# pro_mini_2_clamps.net
KiCad netlist of a schematic drawn in EAGLE
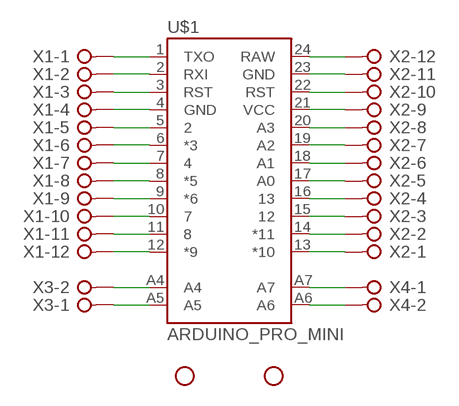
[diagram p0: schematic, sheet 1]

(export (version "E")
  (design (tool "Eeschema 10.0.6"))
  (components
    (comp (ref "STANDOFF1")
      (value "STAND-OFF")
      (footprint "eagle-import:STAND-OFF")
      (libsource (lib "eagle-import") (part "STAND-OFF"))
    )
    (comp (ref "STANDOFF2")
      (value "STAND-OFF")
      (footprint "eagle-import:STAND-OFF")
      (libsource (lib "eagle-import") (part "STAND-OFF"))
    )
    (comp (ref "U$1")
      (value "ARDUINO_PRO_MINI")
      (footprint "eagle-import:ARDUINO_PRO_MINI")
      (libsource (lib "eagle-import") (part "ARDUINO_PRO_MINI"))
    )
    (comp (ref "X1")
      (value "W237-12P")
      (footprint "eagle-import:W237-12P")
      (libsource (lib "eagle-import") (part "W237-12P"))
    )
    (comp (ref "X2")
      (value "W237-12P")
      (footprint "eagle-import:W237-12P")
      (libsource (lib "eagle-import") (part "W237-12P"))
    )
    (comp (ref "X3")
      (value "W237-02P")
      (footprint "eagle-import:W237-132")
      (libsource (lib "eagle-import") (part "W237-02P"))
    )
    (comp (ref "X4")
      (value "W237-02P")
      (footprint "eagle-import:W237-132")
      (libsource (lib "eagle-import") (part "W237-02P"))
    )
  )
  (nets
    (net (code "1") (name "Net-(U$1-*3)") (class "Default")
      (node (ref "U$1") (pin "6") (pinfunction "*3_6") (pintype "bidirectional"))
      (node (ref "X1") (pin "6") (pinfunction "KL_6") (pintype "passive"))
    )
    (net (code "2") (name "Net-(U$1-*5)") (class "Default")
      (node (ref "U$1") (pin "8") (pinfunction "*5_8") (pintype "bidirectional"))
      (node (ref "X1") (pin "8") (pinfunction "KL_8") (pintype "passive"))
    )
    (net (code "3") (name "Net-(U$1-*6)") (class "Default")
      (node (ref "U$1") (pin "9") (pinfunction "*6_9") (pintype "bidirectional"))
      (node (ref "X1") (pin "9") (pinfunction "KL_9") (pintype "passive"))
    )
    (net (code "4") (name "Net-(U$1-*9)") (class "Default")
      (node (ref "U$1") (pin "12") (pinfunction "*9_12") (pintype "bidirectional"))
      (node (ref "X1") (pin "12") (pinfunction "KL_12") (pintype "passive"))
    )
    (net (code "5") (name "Net-(U$1-*10)") (class "Default")
      (node (ref "U$1") (pin "13") (pinfunction "*10_13") (pintype "bidirectional"))
      (node (ref "X2") (pin "1") (pinfunction "KL_1") (pintype "passive"))
    )
    (net (code "6") (name "Net-(U$1-*11)") (class "Default")
      (node (ref "U$1") (pin "14") (pinfunction "*11_14") (pintype "bidirectional"))
      (node (ref "X2") (pin "2") (pinfunction "KL_2") (pintype "passive"))
    )
    (net (code "7") (name "Net-(U$1-2)") (class "Default")
      (node (ref "U$1") (pin "5") (pinfunction "2_5") (pintype "bidirectional"))
      (node (ref "X1") (pin "5") (pinfunction "KL_5") (pintype "passive"))
    )
    (net (code "8") (name "Net-(U$1-4)") (class "Default")
      (node (ref "U$1") (pin "7") (pinfunction "4_7") (pintype "bidirectional"))
      (node (ref "X1") (pin "7") (pinfunction "KL_7") (pintype "passive"))
    )
    (net (code "9") (name "Net-(U$1-7)") (class "Default")
      (node (ref "U$1") (pin "10") (pinfunction "7_10") (pintype "bidirectional"))
      (node (ref "X1") (pin "10") (pinfunction "KL_10") (pintype "passive"))
    )
    (net (code "10") (name "Net-(U$1-8)") (class "Default")
      (node (ref "U$1") (pin "11") (pinfunction "8_11") (pintype "bidirectional"))
      (node (ref "X1") (pin "11") (pinfunction "KL_11") (pintype "passive"))
    )
    (net (code "11") (name "Net-(U$1-12)") (class "Default")
      (node (ref "U$1") (pin "15") (pinfunction "12_15") (pintype "bidirectional"))
      (node (ref "X2") (pin "3") (pinfunction "KL_3") (pintype "passive"))
    )
    (net (code "12") (name "Net-(U$1-13)") (class "Default")
      (node (ref "U$1") (pin "16") (pinfunction "13_16") (pintype "bidirectional"))
      (node (ref "X2") (pin "4") (pinfunction "KL_4") (pintype "passive"))
    )
    (net (code "13") (name "Net-(U$1-A0)") (class "Default")
      (node (ref "U$1") (pin "17") (pinfunction "A0_17") (pintype "bidirectional"))
      (node (ref "X2") (pin "5") (pinfunction "KL_5") (pintype "passive"))
    )
    (net (code "14") (name "Net-(U$1-A1)") (class "Default")
      (node (ref "U$1") (pin "18") (pinfunction "A1_18") (pintype "bidirectional"))
      (node (ref "X2") (pin "6") (pinfunction "KL_6") (pintype "passive"))
    )
    (net (code "15") (name "Net-(U$1-A2)") (class "Default")
      (node (ref "U$1") (pin "19") (pinfunction "A2_19") (pintype "bidirectional"))
      (node (ref "X2") (pin "7") (pinfunction "KL_7") (pintype "passive"))
    )
    (net (code "16") (name "Net-(U$1-A3)") (class "Default")
      (node (ref "U$1") (pin "20") (pinfunction "A3_20") (pintype "bidirectional"))
      (node (ref "X2") (pin "8") (pinfunction "KL_8") (pintype "passive"))
    )
    (net (code "17") (name "Net-(U$1-RAW)") (class "Default")
      (node (ref "U$1") (pin "24") (pinfunction "RAW_24") (pintype "bidirectional"))
      (node (ref "X2") (pin "12") (pinfunction "KL_12") (pintype "passive"))
    )
    (net (code "18") (name "Net-(U$1-RXI)") (class "Default")
      (node (ref "U$1") (pin "2") (pinfunction "RXI_2") (pintype "bidirectional"))
      (node (ref "X1") (pin "2") (pinfunction "KL_2") (pintype "passive"))
    )
    (net (code "19") (name "Net-(U$1-TXO)") (class "Default")
      (node (ref "U$1") (pin "1") (pinfunction "TXO_1") (pintype "bidirectional"))
      (node (ref "X1") (pin "1") (pinfunction "KL_1") (pintype "passive"))
    )
    (net (code "20") (name "Net-(U$1-VCC)") (class "Default")
      (node (ref "U$1") (pin "21") (pinfunction "VCC_21") (pintype "bidirectional"))
      (node (ref "X2") (pin "9") (pinfunction "KL_9") (pintype "passive"))
    )
    (net (code "21") (name "Net-(X1F-KL)") (class "Default")
      (node (ref "U$1") (pin "3") (pinfunction "RST_3") (pintype "bidirectional"))
      (node (ref "X1") (pin "3") (pinfunction "KL_3") (pintype "passive"))
    )
    (net (code "22") (name "Net-(X1G-KL)") (class "Default")
      (node (ref "U$1") (pin "4") (pinfunction "GND_4") (pintype "bidirectional"))
      (node (ref "X1") (pin "4") (pinfunction "KL_4") (pintype "passive"))
    )
    (net (code "23") (name "Net-(X2B-KL)") (class "Default")
      (node (ref "U$1") (pin "22") (pinfunction "RST_22") (pintype "bidirectional"))
      (node (ref "X2") (pin "10") (pinfunction "KL_10") (pintype "passive"))
    )
    (net (code "24") (name "Net-(X2C-KL)") (class "Default")
      (node (ref "U$1") (pin "23") (pinfunction "GND_23") (pintype "bidirectional"))
      (node (ref "X2") (pin "11") (pinfunction "KL_11") (pintype "passive"))
    )
    (net (code "25") (name "Net-(X3A-KL)") (class "Default")
      (node (ref "U$1") (pin "A5") (pinfunction "A5_A5") (pintype "bidirectional"))
      (node (ref "X3") (pin "1") (pinfunction "KL_1") (pintype "passive"))
    )
    (net (code "26") (name "Net-(X3B-KL)") (class "Default")
      (node (ref "U$1") (pin "A4") (pinfunction "A4_A4") (pintype "bidirectional"))
      (node (ref "X3") (pin "2") (pinfunction "KL_2") (pintype "passive"))
    )
    (net (code "27") (name "Net-(X4A-KL)") (class "Default")
      (node (ref "U$1") (pin "A7") (pinfunction "A7_A7") (pintype "bidirectional"))
      (node (ref "X4") (pin "1") (pinfunction "KL_1") (pintype "passive"))
    )
    (net (code "28") (name "Net-(X4B-KL)") (class "Default")
      (node (ref "U$1") (pin "A6") (pinfunction "A6_A6") (pintype "bidirectional"))
      (node (ref "X4") (pin "2") (pinfunction "KL_2") (pintype "passive"))
    )
  )
)
